# Sheet2.net
KiCad netlist of a schematic drawn in Altium Designer
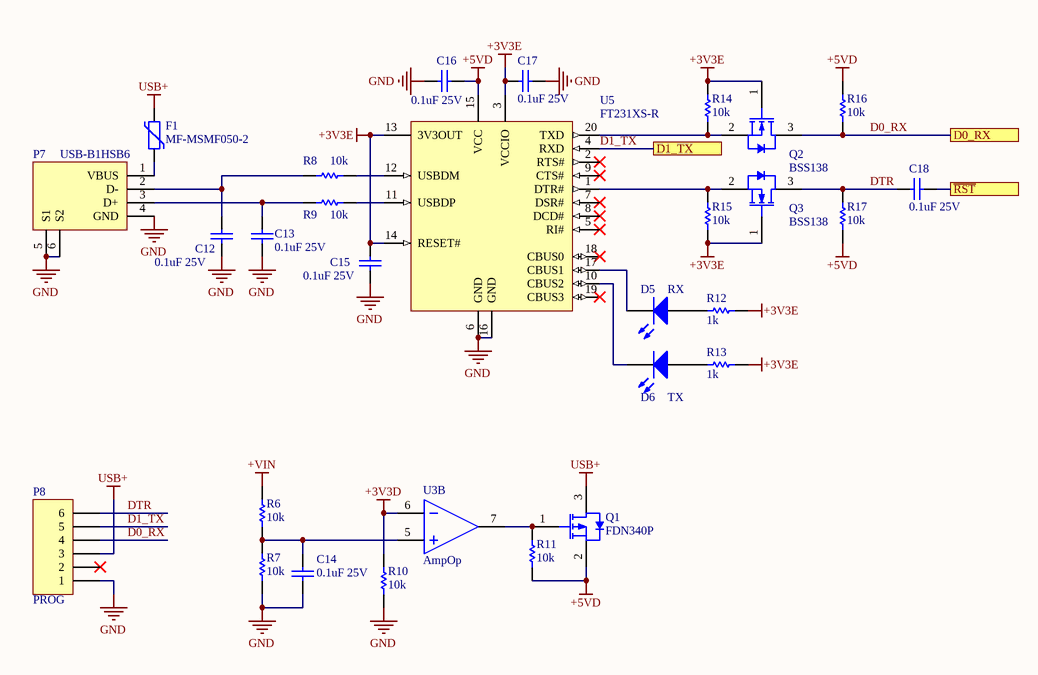
[diagram p0: Sheet2.SchDoc]

(export (version "E")
  (design (tool "Eeschema 10.0.6"))
  (components
    (comp (ref "C12")
      (value "0.1uF 25V")
      (footprint "C1608[0603]")
      (description "Capacitor")
      (fields (field (name "MANUFACTURER PART NUMBER") "GCM188R71E104KA57D") (field (name "TOLERANCE") "10%"))
      (libsource (lib "Basic Library") (part "C"))
    )
    (comp (ref "C13")
      (value "0.1uF 25V")
      (footprint "C1608[0603]")
      (description "Capacitor")
      (fields (field (name "MANUFACTURER PART NUMBER") "GCM188R71E104KA57D") (field (name "TOLERANCE") "10%"))
      (libsource (lib "Basic Library") (part "C"))
    )
    (comp (ref "C14")
      (value "0.1uF 25V")
      (footprint "C1608[0603]")
      (description "Capacitor")
      (fields (field (name "MANUFACTURER PART NUMBER") "GCM188R71E104KA57D") (field (name "TOLERANCE") "10%"))
      (libsource (lib "Basic Library") (part "C"))
    )
    (comp (ref "C15")
      (value "0.1uF 25V")
      (footprint "C1608[0603]")
      (description "Capacitor")
      (fields (field (name "MANUFACTURER PART NUMBER") "GCM188R71E104KA57D") (field (name "TOLERANCE") "10%"))
      (libsource (lib "Basic Library") (part "C"))
    )
    (comp (ref "C16")
      (value "0.1uF 25V")
      (footprint "C1608[0603]")
      (description "Capacitor")
      (fields (field (name "MANUFACTURER PART NUMBER") "GCM188R71E104KA57D") (field (name "TOLERANCE") "10%"))
      (libsource (lib "Basic Library") (part "C"))
    )
    (comp (ref "C17")
      (value "0.1uF 25V")
      (footprint "C1608[0603]")
      (description "Capacitor")
      (fields (field (name "MANUFACTURER PART NUMBER") "GCM188R71E104KA57D") (field (name "TOLERANCE") "10%"))
      (libsource (lib "Basic Library") (part "C"))
    )
    (comp (ref "C18")
      (value "0.1uF 25V")
      (footprint "C1608[0603]")
      (description "Capacitor")
      (fields (field (name "MANUFACTURER PART NUMBER") "GCM188R71E104KA57D") (field (name "TOLERANCE") "10%"))
      (libsource (lib "Basic Library") (part "C"))
    )
    (comp (ref "D5")
      (value "RX")
      (footprint "LED-0603-R")
      (description "LED")
      (fields (field (name "MANUFACTURER PART NUMBER") "LTST-C190KSKT"))
      (libsource (lib "Basic Library") (part "LED"))
    )
    (comp (ref "D6")
      (value "TX")
      (footprint "LED-0603-R")
      (description "LED")
      (fields (field (name "MANUFACTURER PART NUMBER") "LTST-C190KSKT"))
      (libsource (lib "Basic Library") (part "LED"))
    )
    (comp (ref "F1")
      (value "MF-MSMF050-2")
      (footprint "MF-MSMF050")
      (description "Resettable Fuse")
      (libsource (lib "Components Library") (part "MF-MSMF050-2"))
    )
    (comp (ref "P7")
      (value "USB-B1HSB6")
      (footprint "USB_TYPE_B")
      (fields (field (name "MANUFACTURER") "On-Shore Technology"))
      (libsource (lib "Components Library") (part "USB type B"))
    )
    (comp (ref "P8")
      (value "PROG")
      (footprint "HDR1X6m")
      (description "Header, 6-Pin")
      (fields
        (field (name "MANUFACTURER") "Amphenol FCI")
        (field (name "MANUFACTURER PART NUMBER") "68000-406HLF")
        (field (name "PUBLISHER") "Altium Limited")
      )
      (libsource (lib "Connectors Library") (part "Header 6"))
    )
    (comp (ref "Q1")
      (value "FDN340P")
      (footprint "SOT23")
      (description "P-Channel MOSFET")
      (libsource (lib "Basic Library") (part "MOSFET-P"))
    )
    (comp (ref "Q2")
      (value "BSS138")
      (footprint "SOT23")
      (description "N-Channel MOSFET")
      (libsource (lib "Basic Library") (part "MOSFET-N"))
    )
    (comp (ref "Q3")
      (value "BSS138")
      (footprint "SOT23")
      (description "N-Channel MOSFET")
      (libsource (lib "Basic Library") (part "MOSFET-N"))
    )
    (comp (ref "R6")
      (value "10k")
      (footprint "R1608[0603]")
      (description "Resistor")
      (fields (field (name "MANUFACTURER PART NUMBER") "MCT06030C1002FP500") (field (name "TOLERANCE") "1%"))
      (libsource (lib "Basic Library") (part "R"))
    )
    (comp (ref "R7")
      (value "10k")
      (footprint "R1608[0603]")
      (description "Resistor")
      (fields (field (name "MANUFACTURER PART NUMBER") "MCT06030C1002FP500") (field (name "TOLERANCE") "1%"))
      (libsource (lib "Basic Library") (part "R"))
    )
    (comp (ref "R8")
      (value "10k")
      (footprint "R1608[0603]")
      (description "Resistor")
      (fields (field (name "MANUFACTURER PART NUMBER") "MCT06030C1002FP500") (field (name "TOLERANCE") "1%"))
      (libsource (lib "Basic Library") (part "R"))
    )
    (comp (ref "R9")
      (value "10k")
      (footprint "R1608[0603]")
      (description "Resistor")
      (fields (field (name "MANUFACTURER PART NUMBER") "MCT06030C1002FP500") (field (name "TOLERANCE") "1%"))
      (libsource (lib "Basic Library") (part "R"))
    )
    (comp (ref "R10")
      (value "10k")
      (footprint "R1608[0603]")
      (description "Resistor")
      (fields (field (name "MANUFACTURER PART NUMBER") "MCT06030C1002FP500") (field (name "TOLERANCE") "1%"))
      (libsource (lib "Basic Library") (part "R"))
    )
    (comp (ref "R11")
      (value "10k")
      (footprint "R1608[0603]")
      (description "Resistor")
      (fields (field (name "MANUFACTURER PART NUMBER") "MCT06030C1002FP500") (field (name "TOLERANCE") "1%"))
      (libsource (lib "Basic Library") (part "R"))
    )
    (comp (ref "R12")
      (value "1k")
      (footprint "R1608[0603]")
      (description "Resistor")
      (fields (field (name "MANUFACTURER PART NUMBER") "ESR03EZPJ102") (field (name "TOLERANCE") "5%"))
      (libsource (lib "Basic Library") (part "R"))
    )
    (comp (ref "R13")
      (value "1k")
      (footprint "R1608[0603]")
      (description "Resistor")
      (fields (field (name "MANUFACTURER PART NUMBER") "ESR03EZPJ102") (field (name "TOLERANCE") "5%"))
      (libsource (lib "Basic Library") (part "R"))
    )
    (comp (ref "R14")
      (value "10k")
      (footprint "R1608[0603]")
      (description "Resistor")
      (fields (field (name "MANUFACTURER PART NUMBER") "MCT06030C1002FP500") (field (name "TOLERANCE") "1%"))
      (libsource (lib "Basic Library") (part "R"))
    )
    (comp (ref "R15")
      (value "10k")
      (footprint "R1608[0603]")
      (description "Resistor")
      (fields (field (name "MANUFACTURER PART NUMBER") "MCT06030C1002FP500") (field (name "TOLERANCE") "1%"))
      (libsource (lib "Basic Library") (part "R"))
    )
    (comp (ref "R16")
      (value "10k")
      (footprint "R1608[0603]")
      (description "Resistor")
      (fields (field (name "MANUFACTURER PART NUMBER") "MCT06030C1002FP500") (field (name "TOLERANCE") "1%"))
      (libsource (lib "Basic Library") (part "R"))
    )
    (comp (ref "R17")
      (value "10k")
      (footprint "R1608[0603]")
      (description "Resistor")
      (fields (field (name "MANUFACTURER PART NUMBER") "MCT06030C1002FP500") (field (name "TOLERANCE") "1%"))
      (libsource (lib "Basic Library") (part "R"))
    )
    (comp (ref "U3")
      (value "AmpOp")
      (footprint "TSSOP-8")
      (fields
        (field (name "MANUFACTURER") "Texas Instruments")
        (field (name "MANUFACTURER PART NUMBER") "LM358PWR")
      )
      (libsource (lib "Components Library") (part "LM358PWR"))
    )
    (comp (ref "U5")
      (value "FT231XS-R")
      (footprint "NSSOP-20_N")
      (fields (field (name "MANUFACTURER") "FTDI"))
      (libsource (lib "Components Library") (part "FT231XS-R"))
    )
  )
  (nets
    (net (code "1") (name "+3V3D") (class "Default")
      (node (ref "R10") (pin "1") (pinfunction "1_1") (pintype "passive"))
      (node (ref "U3") (pin "6") (pinfunction "IN-_6") (pintype "passive"))
    )
    (net (code "2") (name "+3V3E") (class "Default")
      (node (ref "C15") (pin "2") (pinfunction "2_2") (pintype "passive"))
      (node (ref "C17") (pin "2") (pinfunction "2_2") (pintype "passive"))
      (node (ref "Q2") (pin "1") (pinfunction "GATE_1") (pintype "passive"))
      (node (ref "Q3") (pin "1") (pinfunction "GATE_1") (pintype "passive"))
      (node (ref "R12") (pin "2") (pinfunction "2_2") (pintype "passive"))
      (node (ref "R13") (pin "2") (pinfunction "2_2") (pintype "passive"))
      (node (ref "R14") (pin "1") (pinfunction "1_1") (pintype "passive"))
      (node (ref "R15") (pin "2") (pinfunction "2_2") (pintype "passive"))
      (node (ref "U5") (pin "13") (pinfunction "3V3OUT_13") (pintype "power_in"))
      (node (ref "U5") (pin "14") (pinfunction "RESET#_14") (pintype "input"))
      (node (ref "U5") (pin "3") (pinfunction "VCCIO_3") (pintype "power_in"))
    )
    (net (code "3") (name "+5VD") (class "Default")
      (node (ref "C16") (pin "1") (pinfunction "1_1") (pintype "passive"))
      (node (ref "Q1") (pin "2") (pinfunction "SOURCE_2") (pintype "passive"))
      (node (ref "R11") (pin "2") (pinfunction "2_2") (pintype "passive"))
      (node (ref "R16") (pin "1") (pinfunction "1_1") (pintype "passive"))
      (node (ref "R17") (pin "2") (pinfunction "2_2") (pintype "passive"))
      (node (ref "U5") (pin "15") (pinfunction "VCC_15") (pintype "power_in"))
    )
    (net (code "4") (name "+VIN") (class "Default")
      (node (ref "R6") (pin "1") (pinfunction "1_1") (pintype "passive"))
    )
    (net (code "5") (name "/D0_RX") (class "Default")
      (node (ref "P8") (pin "4") (pinfunction "4_4") (pintype "passive"))
      (node (ref "Q2") (pin "3") (pinfunction "DRAIN_3") (pintype "passive"))
      (node (ref "R16") (pin "2") (pinfunction "2_2") (pintype "passive"))
    )
    (net (code "6") (name "/D1_TX") (class "Default")
      (node (ref "P8") (pin "5") (pinfunction "5_5") (pintype "passive"))
      (node (ref "U5") (pin "4") (pinfunction "RXD_4") (pintype "input"))
    )
    (net (code "7") (name "/DTR") (class "Default")
      (node (ref "C18") (pin "1") (pinfunction "1_1") (pintype "passive"))
      (node (ref "P8") (pin "6") (pinfunction "6_6") (pintype "passive"))
      (node (ref "Q3") (pin "3") (pinfunction "DRAIN_3") (pintype "passive"))
      (node (ref "R17") (pin "1") (pinfunction "1_1") (pintype "passive"))
    )
    (net (code "8") (name "/~{RST}") (class "Default")
      (node (ref "C18") (pin "2") (pinfunction "2_2") (pintype "passive"))
    )
    (net (code "9") (name "GND") (class "Default")
      (node (ref "C12") (pin "2") (pinfunction "2_2") (pintype "passive"))
      (node (ref "C13") (pin "2") (pinfunction "2_2") (pintype "passive"))
      (node (ref "C14") (pin "1") (pinfunction "1_1") (pintype "passive"))
      (node (ref "C15") (pin "1") (pinfunction "1_1") (pintype "passive"))
      (node (ref "C16") (pin "2") (pinfunction "2_2") (pintype "passive"))
      (node (ref "C17") (pin "1") (pinfunction "1_1") (pintype "passive"))
      (node (ref "P7") (pin "4") (pinfunction "GND_4") (pintype "passive"))
      (node (ref "P7") (pin "5") (pinfunction "S1_5") (pintype "passive"))
      (node (ref "P7") (pin "6") (pinfunction "S2_6") (pintype "passive"))
      (node (ref "P8") (pin "1") (pinfunction "1_1") (pintype "passive"))
      (node (ref "R10") (pin "2") (pinfunction "2_2") (pintype "passive"))
      (node (ref "R7") (pin "2") (pinfunction "2_2") (pintype "passive"))
      (node (ref "U5") (pin "16") (pinfunction "GND_16") (pintype "power_in"))
      (node (ref "U5") (pin "6") (pinfunction "GND_6") (pintype "power_in"))
    )
    (net (code "10") (name "Net-(D5-A)") (class "Default")
      (node (ref "D5") (pin "1") (pinfunction "A_1") (pintype "passive"))
      (node (ref "R12") (pin "1") (pinfunction "1_1") (pintype "passive"))
    )
    (net (code "11") (name "Net-(D5-K)") (class "Default")
      (node (ref "D5") (pin "2") (pinfunction "K_2") (pintype "passive"))
      (node (ref "U5") (pin "17") (pinfunction "CBUS1_17") (pintype "bidirectional"))
    )
    (net (code "12") (name "Net-(D6-A)") (class "Default")
      (node (ref "D6") (pin "1") (pinfunction "A_1") (pintype "passive"))
      (node (ref "R13") (pin "1") (pinfunction "1_1") (pintype "passive"))
    )
    (net (code "13") (name "Net-(D6-K)") (class "Default")
      (node (ref "D6") (pin "2") (pinfunction "K_2") (pintype "passive"))
      (node (ref "U5") (pin "10") (pinfunction "CBUS2_10") (pintype "bidirectional"))
    )
    (net (code "14") (name "Net-(P7-D+)") (class "Default")
      (node (ref "C13") (pin "1") (pinfunction "1_1") (pintype "passive"))
      (node (ref "P7") (pin "3") (pinfunction "D+_3") (pintype "passive"))
      (node (ref "R9") (pin "2") (pinfunction "2_2") (pintype "passive"))
    )
    (net (code "15") (name "Net-(P7-D-)") (class "Default")
      (node (ref "C12") (pin "1") (pinfunction "1_1") (pintype "passive"))
      (node (ref "P7") (pin "2") (pinfunction "D-_2") (pintype "passive"))
      (node (ref "R8") (pin "2") (pinfunction "2_2") (pintype "passive"))
    )
    (net (code "16") (name "Net-(P7-VBUS)") (class "Default")
      (node (ref "F1") (pin "1") (pinfunction "1_1") (pintype "passive"))
      (node (ref "P7") (pin "1") (pinfunction "VBUS_1") (pintype "passive"))
    )
    (net (code "17") (name "Net-(Q1-GATE)") (class "Default")
      (node (ref "Q1") (pin "1") (pinfunction "GATE_1") (pintype "passive"))
      (node (ref "R11") (pin "1") (pinfunction "1_1") (pintype "passive"))
      (node (ref "U3") (pin "7") (pinfunction "OUT_7") (pintype "passive"))
    )
    (net (code "18") (name "Net-(Q2-SOURCE)") (class "Default")
      (node (ref "Q2") (pin "2") (pinfunction "SOURCE_2") (pintype "passive"))
      (node (ref "R14") (pin "2") (pinfunction "2_2") (pintype "passive"))
      (node (ref "U5") (pin "20") (pinfunction "TXD_20") (pintype "output"))
    )
    (net (code "19") (name "Net-(Q3-SOURCE)") (class "Default")
      (node (ref "Q3") (pin "2") (pinfunction "SOURCE_2") (pintype "passive"))
      (node (ref "R15") (pin "1") (pinfunction "1_1") (pintype "passive"))
      (node (ref "U5") (pin "1") (pinfunction "DTR#_1") (pintype "output"))
    )
    (net (code "20") (name "Net-(U3B-IN+)") (class "Default")
      (node (ref "C14") (pin "2") (pinfunction "2_2") (pintype "passive"))
      (node (ref "R6") (pin "2") (pinfunction "2_2") (pintype "passive"))
      (node (ref "R7") (pin "1") (pinfunction "1_1") (pintype "passive"))
      (node (ref "U3") (pin "5") (pinfunction "IN+_5") (pintype "passive"))
    )
    (net (code "21") (name "Net-(U5-USBDM)") (class "Default")
      (node (ref "R8") (pin "1") (pinfunction "1_1") (pintype "passive"))
      (node (ref "U5") (pin "12") (pinfunction "USBDM_12") (pintype "input"))
    )
    (net (code "22") (name "Net-(U5-USBDP)") (class "Default")
      (node (ref "R9") (pin "1") (pinfunction "1_1") (pintype "passive"))
      (node (ref "U5") (pin "11") (pinfunction "USBDP_11") (pintype "input"))
    )
    (net (code "23") (name "USB+") (class "Default")
      (node (ref "F1") (pin "2") (pinfunction "2_2") (pintype "passive"))
      (node (ref "P8") (pin "3") (pinfunction "3_3") (pintype "passive"))
      (node (ref "Q1") (pin "3") (pinfunction "DRAIN_3") (pintype "passive"))
    )
    (net (code "24") (name "unconnected-(P8-Pad2)") (class "Default")
      (node (ref "P8") (pin "2") (pinfunction "2_2") (pintype "passive+no_connect"))
    )
    (net (code "25") (name "unconnected-(U5-CBUS0-Pad18)") (class "Default")
      (node (ref "U5") (pin "18") (pinfunction "CBUS0_18") (pintype "bidirectional+no_connect"))
    )
    (net (code "26") (name "unconnected-(U5-CBUS3-Pad19)") (class "Default")
      (node (ref "U5") (pin "19") (pinfunction "CBUS3_19") (pintype "bidirectional+no_connect"))
    )
    (net (code "27") (name "unconnected-(U5-CTS#-Pad9)") (class "Default")
      (node (ref "U5") (pin "9") (pinfunction "CTS#_9") (pintype "input+no_connect"))
    )
    (net (code "28") (name "unconnected-(U5-DCD#-Pad8)") (class "Default")
      (node (ref "U5") (pin "8") (pinfunction "DCD#_8") (pintype "input+no_connect"))
    )
    (net (code "29") (name "unconnected-(U5-DSR#-Pad7)") (class "Default")
      (node (ref "U5") (pin "7") (pinfunction "DSR#_7") (pintype "input+no_connect"))
    )
    (net (code "30") (name "unconnected-(U5-RI#-Pad5)") (class "Default")
      (node (ref "U5") (pin "5") (pinfunction "RI#_5") (pintype "input+no_connect"))
    )
    (net (code "31") (name "unconnected-(U5-RTS#-Pad2)") (class "Default")
      (node (ref "U5") (pin "2") (pinfunction "RTS#_2") (pintype "output+no_connect"))
    )
  )
)
